# HSHV4-student_version.net
KiCad netlist of a schematic drawn in EAGLE
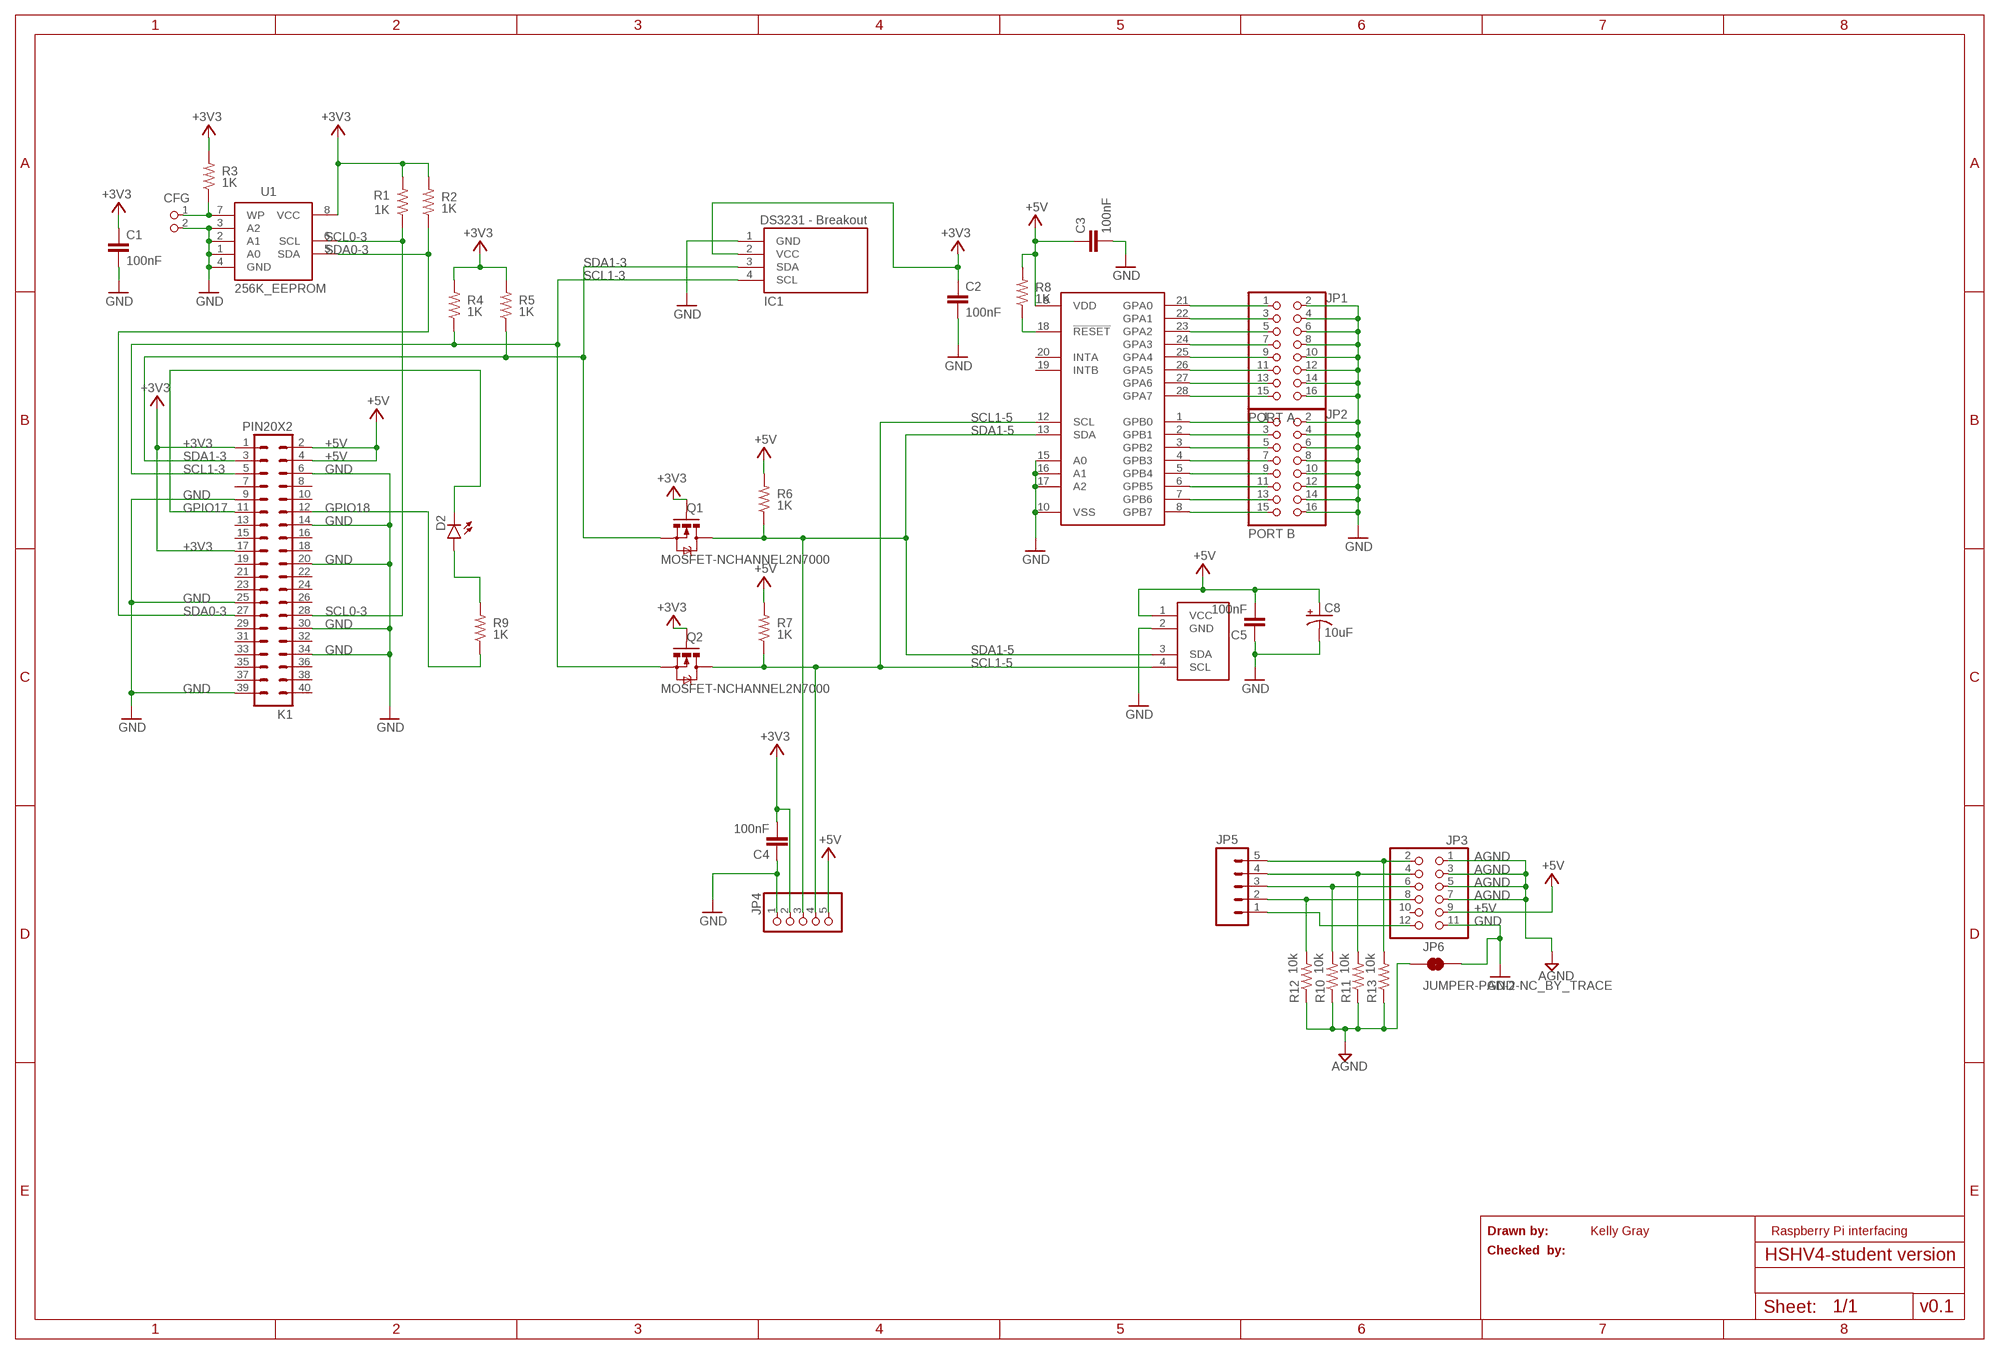
[diagram p0: schematic, sheet 1]

(export (version "E")
  (design (tool "Eeschema 10.0.6"))
  (components
    (comp (ref "C1")
      (value "100nF")
      (footprint "eagle-import:CAP-PTH-SMALL-KIT")
      (libsource (lib "eagle-import") (part "0.1UF-50V-20%(PTH)KIT-EZ"))
    )
    (comp (ref "C2")
      (value "100nF")
      (footprint "eagle-import:CAP-PTH-SMALL-KIT")
      (libsource (lib "eagle-import") (part "0.1UF-50V-20%(PTH)KIT-EZ"))
    )
    (comp (ref "C3")
      (value "100nF")
      (footprint "eagle-import:CAP-PTH-SMALL-KIT")
      (libsource (lib "eagle-import") (part "0.1UF-50V-20%(PTH)KIT-EZ"))
    )
    (comp (ref "C4")
      (value "100nF")
      (footprint "eagle-import:CAP-PTH-SMALL-KIT")
      (libsource (lib "eagle-import") (part "0.1UF-50V-20%(PTH)KIT-EZ"))
    )
    (comp (ref "C5")
      (value "100nF")
      (footprint "eagle-import:CAP-PTH-SMALL-KIT")
      (libsource (lib "eagle-import") (part "0.1UF-50V-20%(PTH)KIT-EZ"))
    )
    (comp (ref "C8")
      (value "10uF")
      (footprint "eagle-import:CPOL-RADIAL-10UF-25V")
      (libsource (lib "eagle-import") (part "10UF-25V-20%(PTH)"))
    )
    (comp (ref "CFG")
      (value "PIN2_100")
      (footprint "eagle-import:PIN_W_2")
      (libsource (lib "eagle-import") (part "PIN2_100"))
    )
    (comp (ref "D2")
      (value "LED-3MM-NO_SILK")
      (footprint "eagle-import:LED3MM-NS")
      (libsource (lib "eagle-import") (part "LED-3MM-NO_SILK"))
    )
    (comp (ref "IC1")
      (value "DS3231")
      (footprint "eagle-import:8PTH")
      (libsource (lib "eagle-import") (part "DS3231"))
    )
    (comp (ref "IC4")
      (value "IO_EXPANDER")
      (footprint "eagle-import:DIL28-3")
      (libsource (lib "eagle-import") (part "IO_EXPANDER"))
    )
    (comp (ref "JP1")
      (value "PORT A")
      (footprint "eagle-import:2X08")
      (libsource (lib "eagle-import") (part "PINHD-2X8"))
    )
    (comp (ref "JP2")
      (value "PORT B")
      (footprint "eagle-import:2X08")
      (libsource (lib "eagle-import") (part "PINHD-2X8"))
    )
    (comp (ref "JP3")
      (value "PINHD-2X6")
      (footprint "eagle-import:2X06")
      (libsource (lib "eagle-import") (part "PINHD-2X6"))
    )
    (comp (ref "JP4")
      (value "PINHD-1X5")
      (footprint "eagle-import:1X05")
      (libsource (lib "eagle-import") (part "PINHD-1X5"))
    )
    (comp (ref "JP5")
      (value "M05PTH")
      (footprint "eagle-import:1X05")
      (libsource (lib "eagle-import") (part "M05PTH"))
    )
    (comp (ref "JP6")
      (value "JUMPER-PAD-2-NC_BY_TRACE")
      (footprint "eagle-import:PAD-JUMPER-2-NC_BY_TRACE_YES_SILK")
      (libsource (lib "eagle-import") (part "JUMPER-PAD-2-NC_BY_TRACE"))
    )
    (comp (ref "K1")
      (value "PIN20X2")
      (footprint "eagle-import:PIN_20X2")
      (libsource (lib "eagle-import") (part "PIN20X2"))
    )
    (comp (ref "Q1")
      (value "MOSFET-NCHANNEL2N7000")
      (footprint "eagle-import:TO-92")
      (libsource (lib "eagle-import") (part "MOSFET-NCHANNEL2N7000"))
    )
    (comp (ref "Q2")
      (value "MOSFET-NCHANNEL2N7000")
      (footprint "eagle-import:TO-92")
      (libsource (lib "eagle-import") (part "MOSFET-NCHANNEL2N7000"))
    )
    (comp (ref "R1")
      (value "1K")
      (footprint "eagle-import:AXIAL-0.3")
      (fields (field (name "TOLERANCE") "5%"))
      (libsource (lib "eagle-import") (part "1KOHM-1/4W-1%(PTH)"))
    )
    (comp (ref "R2")
      (value "1K")
      (footprint "eagle-import:AXIAL-0.3")
      (fields (field (name "TOLERANCE") "5%"))
      (libsource (lib "eagle-import") (part "1KOHM-1/4W-1%(PTH)"))
    )
    (comp (ref "R3")
      (value "1K")
      (footprint "eagle-import:AXIAL-0.3")
      (fields (field (name "TOLERANCE") "5%"))
      (libsource (lib "eagle-import") (part "1KOHM-1/4W-1%(PTH)"))
    )
    (comp (ref "R4")
      (value "1K")
      (footprint "eagle-import:AXIAL-0.3")
      (fields (field (name "TOLERANCE") "5%"))
      (libsource (lib "eagle-import") (part "1KOHM-1/4W-1%(PTH)"))
    )
    (comp (ref "R5")
      (value "1K")
      (footprint "eagle-import:AXIAL-0.3")
      (fields (field (name "TOLERANCE") "5%"))
      (libsource (lib "eagle-import") (part "1KOHM-1/4W-1%(PTH)"))
    )
    (comp (ref "R6")
      (value "1K")
      (footprint "eagle-import:AXIAL-0.3")
      (fields (field (name "TOLERANCE") "5%"))
      (libsource (lib "eagle-import") (part "1KOHM-1/4W-1%(PTH)"))
    )
    (comp (ref "R7")
      (value "1K")
      (footprint "eagle-import:AXIAL-0.3")
      (fields (field (name "TOLERANCE") "5%"))
      (libsource (lib "eagle-import") (part "1KOHM-1/4W-1%(PTH)"))
    )
    (comp (ref "R8")
      (value "1K")
      (footprint "eagle-import:AXIAL-0.3")
      (fields (field (name "TOLERANCE") "5%"))
      (libsource (lib "eagle-import") (part "1KOHM-1/4W-1%(PTH)"))
    )
    (comp (ref "R9")
      (value "1K")
      (footprint "eagle-import:AXIAL-0.3")
      (fields (field (name "TOLERANCE") "5%"))
      (libsource (lib "eagle-import") (part "1KOHM-1/4W-1%(PTH)"))
    )
    (comp (ref "R10")
      (value "10k")
      (footprint "eagle-import:AXIAL-0.3")
      (fields (field (name "TOLERANCE") "5%"))
      (libsource (lib "eagle-import") (part "10KOHM-1/4W-1%(PTH)HORIZ"))
    )
    (comp (ref "R11")
      (value "10k")
      (footprint "eagle-import:AXIAL-0.3")
      (fields (field (name "TOLERANCE") "5%"))
      (libsource (lib "eagle-import") (part "10KOHM-1/4W-1%(PTH)HORIZ"))
    )
    (comp (ref "R12")
      (value "10k")
      (footprint "eagle-import:AXIAL-0.3")
      (fields (field (name "TOLERANCE") "5%"))
      (libsource (lib "eagle-import") (part "10KOHM-1/4W-1%(PTH)HORIZ"))
    )
    (comp (ref "R13")
      (value "10k")
      (footprint "eagle-import:AXIAL-0.3")
      (fields (field (name "TOLERANCE") "5%"))
      (libsource (lib "eagle-import") (part "10KOHM-1/4W-1%(PTH)HORIZ"))
    )
    (comp (ref "U$1")
      (value "PCF8591")
      (footprint "eagle-import:1X04")
      (libsource (lib "eagle-import") (part "PCF8591"))
    )
    (comp (ref "U1")
      (value "256K_EEPROM")
      (footprint "eagle-import:DIL08")
      (libsource (lib "eagle-import") (part "256K_EEPROM"))
    )
  )
  (nets
    (net (code "1") (name "+3V3") (class "Default")
      (node (ref "C1") (pin "1") (pinfunction "1_1") (pintype "passive"))
      (node (ref "C2") (pin "1") (pinfunction "1_1") (pintype "passive"))
      (node (ref "C4") (pin "2") (pinfunction "2_2") (pintype "passive"))
      (node (ref "IC1") (pin "2") (pinfunction "VCC_2") (pintype "power_in"))
      (node (ref "JP4") (pin "2") (pinfunction "2_2") (pintype "passive"))
      (node (ref "K1") (pin "1") (pinfunction "1_1") (pintype "passive"))
      (node (ref "K1") (pin "17") (pinfunction "17_17") (pintype "passive"))
      (node (ref "Q1") (pin "2") (pinfunction "G_2") (pintype "passive"))
      (node (ref "Q2") (pin "2") (pinfunction "G_2") (pintype "passive"))
      (node (ref "R1") (pin "P$2") (pinfunction "2_P$2") (pintype "passive"))
      (node (ref "R2") (pin "P$2") (pinfunction "2_P$2") (pintype "passive"))
      (node (ref "R3") (pin "P$2") (pinfunction "2_P$2") (pintype "passive"))
      (node (ref "R4") (pin "P$2") (pinfunction "2_P$2") (pintype "passive"))
      (node (ref "R5") (pin "P$2") (pinfunction "2_P$2") (pintype "passive"))
      (node (ref "U1") (pin "8") (pinfunction "VCC_8") (pintype "bidirectional"))
    )
    (net (code "2") (name "+5V") (class "Default")
      (node (ref "C3") (pin "1") (pinfunction "1_1") (pintype "passive"))
      (node (ref "C5") (pin "2") (pinfunction "2_2") (pintype "passive"))
      (node (ref "C8") (pin "1") (pinfunction "+_1") (pintype "passive"))
      (node (ref "IC4") (pin "9") (pinfunction "VDD_9") (pintype "bidirectional"))
      (node (ref "JP3") (pin "9") (pinfunction "9_9") (pintype "passive"))
      (node (ref "JP4") (pin "5") (pinfunction "5_5") (pintype "passive"))
      (node (ref "K1") (pin "2") (pinfunction "2_2") (pintype "passive"))
      (node (ref "K1") (pin "4") (pinfunction "4_4") (pintype "passive"))
      (node (ref "R6") (pin "P$2") (pinfunction "2_P$2") (pintype "passive"))
      (node (ref "R7") (pin "P$2") (pinfunction "2_P$2") (pintype "passive"))
      (node (ref "R8") (pin "P$2") (pinfunction "2_P$2") (pintype "passive"))
      (node (ref "U$1") (pin "1") (pinfunction "VCC_1") (pintype "bidirectional"))
    )
    (net (code "3") (name "/GPIO17") (class "Default")
      (node (ref "D2") (pin "K") (pinfunction "C_K") (pintype "passive"))
      (node (ref "K1") (pin "11") (pinfunction "11_11") (pintype "passive"))
    )
    (net (code "4") (name "/GPIO18") (class "Default")
      (node (ref "K1") (pin "12") (pinfunction "12_12") (pintype "passive"))
      (node (ref "R9") (pin "P$1") (pinfunction "1_P$1") (pintype "passive"))
    )
    (net (code "5") (name "/SCL0-3") (class "Default")
      (node (ref "K1") (pin "28") (pinfunction "28_28") (pintype "passive"))
      (node (ref "R1") (pin "P$1") (pinfunction "1_P$1") (pintype "passive"))
      (node (ref "U1") (pin "6") (pinfunction "SCL_6") (pintype "bidirectional"))
    )
    (net (code "6") (name "/SCL1-3") (class "Default")
      (node (ref "IC1") (pin "4") (pinfunction "SCL_4") (pintype "bidirectional"))
      (node (ref "K1") (pin "5") (pinfunction "5_5") (pintype "passive"))
      (node (ref "Q2") (pin "1") (pinfunction "S_1") (pintype "passive"))
      (node (ref "R4") (pin "P$1") (pinfunction "1_P$1") (pintype "passive"))
    )
    (net (code "7") (name "/SCL1-5") (class "Default")
      (node (ref "IC4") (pin "12") (pinfunction "SCL_12") (pintype "bidirectional"))
      (node (ref "JP4") (pin "4") (pinfunction "4_4") (pintype "passive"))
      (node (ref "Q2") (pin "3") (pinfunction "D_3") (pintype "passive"))
      (node (ref "R7") (pin "P$1") (pinfunction "1_P$1") (pintype "passive"))
      (node (ref "U$1") (pin "4") (pinfunction "SCL_4") (pintype "bidirectional"))
    )
    (net (code "8") (name "/SDA0-3") (class "Default")
      (node (ref "K1") (pin "27") (pinfunction "27_27") (pintype "passive"))
      (node (ref "R2") (pin "P$1") (pinfunction "1_P$1") (pintype "passive"))
      (node (ref "U1") (pin "5") (pinfunction "SDA_5") (pintype "bidirectional"))
    )
    (net (code "9") (name "/SDA1-3") (class "Default")
      (node (ref "IC1") (pin "3") (pinfunction "SDA_3") (pintype "bidirectional"))
      (node (ref "K1") (pin "3") (pinfunction "3_3") (pintype "passive"))
      (node (ref "Q1") (pin "1") (pinfunction "S_1") (pintype "passive"))
      (node (ref "R5") (pin "P$1") (pinfunction "1_P$1") (pintype "passive"))
    )
    (net (code "10") (name "/SDA1-5") (class "Default")
      (node (ref "IC4") (pin "13") (pinfunction "SDA_13") (pintype "bidirectional"))
      (node (ref "JP4") (pin "3") (pinfunction "3_3") (pintype "passive"))
      (node (ref "Q1") (pin "3") (pinfunction "D_3") (pintype "passive"))
      (node (ref "R6") (pin "P$1") (pinfunction "1_P$1") (pintype "passive"))
      (node (ref "U$1") (pin "3") (pinfunction "SDA_3") (pintype "bidirectional"))
    )
    (net (code "11") (name "AGND") (class "Default")
      (node (ref "JP3") (pin "1") (pinfunction "1_1") (pintype "passive"))
      (node (ref "JP3") (pin "3") (pinfunction "3_3") (pintype "passive"))
      (node (ref "JP3") (pin "5") (pinfunction "5_5") (pintype "passive"))
      (node (ref "JP3") (pin "7") (pinfunction "7_7") (pintype "passive"))
      (node (ref "JP6") (pin "1") (pinfunction "1_1") (pintype "passive"))
      (node (ref "R10") (pin "P$1") (pinfunction "1_P$1") (pintype "passive"))
      (node (ref "R11") (pin "P$1") (pinfunction "1_P$1") (pintype "passive"))
      (node (ref "R12") (pin "P$1") (pinfunction "1_P$1") (pintype "passive"))
      (node (ref "R13") (pin "P$1") (pinfunction "1_P$1") (pintype "passive"))
    )
    (net (code "12") (name "GND") (class "Default")
      (node (ref "C1") (pin "2") (pinfunction "2_2") (pintype "passive"))
      (node (ref "C2") (pin "2") (pinfunction "2_2") (pintype "passive"))
      (node (ref "C3") (pin "2") (pinfunction "2_2") (pintype "passive"))
      (node (ref "C4") (pin "1") (pinfunction "1_1") (pintype "passive"))
      (node (ref "C5") (pin "1") (pinfunction "1_1") (pintype "passive"))
      (node (ref "C8") (pin "2") (pinfunction "-_2") (pintype "passive"))
      (node (ref "CFG") (pin "2") (pinfunction "2_2") (pintype "passive"))
      (node (ref "IC1") (pin "1") (pinfunction "GND_1") (pintype "power_in"))
      (node (ref "IC4") (pin "10") (pinfunction "VSS_10") (pintype "bidirectional"))
      (node (ref "IC4") (pin "15") (pinfunction "A0_15") (pintype "bidirectional"))
      (node (ref "IC4") (pin "16") (pinfunction "A1_16") (pintype "bidirectional"))
      (node (ref "IC4") (pin "17") (pinfunction "A2_17") (pintype "bidirectional"))
      (node (ref "JP1") (pin "10") (pinfunction "10_10") (pintype "passive"))
      (node (ref "JP1") (pin "12") (pinfunction "12_12") (pintype "passive"))
      (node (ref "JP1") (pin "14") (pinfunction "14_14") (pintype "passive"))
      (node (ref "JP1") (pin "16") (pinfunction "16_16") (pintype "passive"))
      (node (ref "JP1") (pin "2") (pinfunction "2_2") (pintype "passive"))
      (node (ref "JP1") (pin "4") (pinfunction "4_4") (pintype "passive"))
      (node (ref "JP1") (pin "6") (pinfunction "6_6") (pintype "passive"))
      (node (ref "JP1") (pin "8") (pinfunction "8_8") (pintype "passive"))
      (node (ref "JP2") (pin "10") (pinfunction "10_10") (pintype "passive"))
      (node (ref "JP2") (pin "12") (pinfunction "12_12") (pintype "passive"))
      (node (ref "JP2") (pin "14") (pinfunction "14_14") (pintype "passive"))
      (node (ref "JP2") (pin "16") (pinfunction "16_16") (pintype "passive"))
      (node (ref "JP2") (pin "2") (pinfunction "2_2") (pintype "passive"))
      (node (ref "JP2") (pin "4") (pinfunction "4_4") (pintype "passive"))
      (node (ref "JP2") (pin "6") (pinfunction "6_6") (pintype "passive"))
      (node (ref "JP2") (pin "8") (pinfunction "8_8") (pintype "passive"))
      (node (ref "JP3") (pin "11") (pinfunction "11_11") (pintype "passive"))
      (node (ref "JP4") (pin "1") (pinfunction "1_1") (pintype "passive"))
      (node (ref "JP6") (pin "2") (pinfunction "2_2") (pintype "passive"))
      (node (ref "K1") (pin "14") (pinfunction "14_14") (pintype "passive"))
      (node (ref "K1") (pin "20") (pinfunction "20_20") (pintype "passive"))
      (node (ref "K1") (pin "25") (pinfunction "25_25") (pintype "passive"))
      (node (ref "K1") (pin "30") (pinfunction "30_30") (pintype "passive"))
      (node (ref "K1") (pin "34") (pinfunction "34_34") (pintype "passive"))
      (node (ref "K1") (pin "39") (pinfunction "39_39") (pintype "passive"))
      (node (ref "K1") (pin "6") (pinfunction "6_6") (pintype "passive"))
      (node (ref "K1") (pin "9") (pinfunction "9_9") (pintype "passive"))
      (node (ref "U$1") (pin "2") (pinfunction "GND_2") (pintype "bidirectional"))
      (node (ref "U1") (pin "1") (pinfunction "A0_1") (pintype "bidirectional"))
      (node (ref "U1") (pin "2") (pinfunction "A1_2") (pintype "bidirectional"))
      (node (ref "U1") (pin "3") (pinfunction "A2_3") (pintype "bidirectional"))
      (node (ref "U1") (pin "4") (pinfunction "GND_4") (pintype "bidirectional"))
    )
    (net (code "13") (name "Net-(IC4-GPA0)") (class "Default")
      (node (ref "IC4") (pin "21") (pinfunction "GPA0_21") (pintype "bidirectional"))
      (node (ref "JP1") (pin "1") (pinfunction "1_1") (pintype "passive"))
    )
    (net (code "14") (name "Net-(IC4-GPA1)") (class "Default")
      (node (ref "IC4") (pin "22") (pinfunction "GPA1_22") (pintype "bidirectional"))
      (node (ref "JP1") (pin "3") (pinfunction "3_3") (pintype "passive"))
    )
    (net (code "15") (name "Net-(IC4-GPA2)") (class "Default")
      (node (ref "IC4") (pin "23") (pinfunction "GPA2_23") (pintype "bidirectional"))
      (node (ref "JP1") (pin "5") (pinfunction "5_5") (pintype "passive"))
    )
    (net (code "16") (name "Net-(IC4-GPA3)") (class "Default")
      (node (ref "IC4") (pin "24") (pinfunction "GPA3_24") (pintype "bidirectional"))
      (node (ref "JP1") (pin "7") (pinfunction "7_7") (pintype "passive"))
    )
    (net (code "17") (name "Net-(IC4-GPA4)") (class "Default")
      (node (ref "IC4") (pin "25") (pinfunction "GPA4_25") (pintype "bidirectional"))
      (node (ref "JP1") (pin "9") (pinfunction "9_9") (pintype "passive"))
    )
    (net (code "18") (name "Net-(IC4-GPA5)") (class "Default")
      (node (ref "IC4") (pin "26") (pinfunction "GPA5_26") (pintype "bidirectional"))
      (node (ref "JP1") (pin "11") (pinfunction "11_11") (pintype "passive"))
    )
    (net (code "19") (name "Net-(IC4-GPA6)") (class "Default")
      (node (ref "IC4") (pin "27") (pinfunction "GPA6_27") (pintype "bidirectional"))
      (node (ref "JP1") (pin "13") (pinfunction "13_13") (pintype "passive"))
    )
    (net (code "20") (name "Net-(IC4-GPA7)") (class "Default")
      (node (ref "IC4") (pin "28") (pinfunction "GPA7_28") (pintype "bidirectional"))
      (node (ref "JP1") (pin "15") (pinfunction "15_15") (pintype "passive"))
    )
    (net (code "21") (name "Net-(IC4-GPB0)") (class "Default")
      (node (ref "IC4") (pin "1") (pinfunction "GPB0_1") (pintype "bidirectional"))
      (node (ref "JP2") (pin "1") (pinfunction "1_1") (pintype "passive"))
    )
    (net (code "22") (name "Net-(IC4-GPB1)") (class "Default")
      (node (ref "IC4") (pin "2") (pinfunction "GPB1_2") (pintype "bidirectional"))
      (node (ref "JP2") (pin "3") (pinfunction "3_3") (pintype "passive"))
    )
    (net (code "23") (name "Net-(IC4-GPB2)") (class "Default")
      (node (ref "IC4") (pin "3") (pinfunction "GPB2_3") (pintype "bidirectional"))
      (node (ref "JP2") (pin "5") (pinfunction "5_5") (pintype "passive"))
    )
    (net (code "24") (name "Net-(IC4-GPB3)") (class "Default")
      (node (ref "IC4") (pin "4") (pinfunction "GPB3_4") (pintype "bidirectional"))
      (node (ref "JP2") (pin "7") (pinfunction "7_7") (pintype "passive"))
    )
    (net (code "25") (name "Net-(IC4-GPB4)") (class "Default")
      (node (ref "IC4") (pin "5") (pinfunction "GPB4_5") (pintype "bidirectional"))
      (node (ref "JP2") (pin "9") (pinfunction "9_9") (pintype "passive"))
    )
    (net (code "26") (name "Net-(IC4-GPB5)") (class "Default")
      (node (ref "IC4") (pin "6") (pinfunction "GPB5_6") (pintype "bidirectional"))
      (node (ref "JP2") (pin "11") (pinfunction "11_11") (pintype "passive"))
    )
    (net (code "27") (name "Net-(IC4-GPB6)") (class "Default")
      (node (ref "IC4") (pin "7") (pinfunction "GPB6_7") (pintype "bidirectional"))
      (node (ref "JP2") (pin "13") (pinfunction "13_13") (pintype "passive"))
    )
    (net (code "28") (name "Net-(IC4-GPB7)") (class "Default")
      (node (ref "IC4") (pin "8") (pinfunction "GPB7_8") (pintype "bidirectional"))
      (node (ref "JP2") (pin "15") (pinfunction "15_15") (pintype "passive"))
    )
    (net (code "29") (name "Net-(IC4-~{RESET})") (class "Default")
      (node (ref "IC4") (pin "18") (pinfunction "~{RESET}_18") (pintype "bidirectional"))
      (node (ref "R8") (pin "P$1") (pinfunction "1_P$1") (pintype "passive"))
    )
    (net (code "30") (name "Net-(JP3-Pad12)") (class "Default")
      (node (ref "JP3") (pin "12") (pinfunction "12_12") (pintype "passive"))
      (node (ref "JP5") (pin "1") (pinfunction "1_1") (pintype "passive"))
    )
    (net (code "31") (name "Net-(R3-1)") (class "Default")
      (node (ref "CFG") (pin "1") (pinfunction "1_1") (pintype "passive"))
      (node (ref "R3") (pin "P$1") (pinfunction "1_P$1") (pintype "passive"))
      (node (ref "U1") (pin "7") (pinfunction "WP_7") (pintype "bidirectional"))
    )
    (net (code "32") (name "Net-(R9-2)") (class "Default")
      (node (ref "D2") (pin "A") (pinfunction "A_A") (pintype "passive"))
      (node (ref "R9") (pin "P$2") (pinfunction "2_P$2") (pintype "passive"))
    )
    (net (code "33") (name "Net-(R10-2)") (class "Default")
      (node (ref "JP3") (pin "6") (pinfunction "6_6") (pintype "passive"))
      (node (ref "JP5") (pin "3") (pinfunction "3_3") (pintype "passive"))
      (node (ref "R10") (pin "P$2") (pinfunction "2_P$2") (pintype "passive"))
    )
    (net (code "34") (name "Net-(R11-2)") (class "Default")
      (node (ref "JP3") (pin "4") (pinfunction "4_4") (pintype "passive"))
      (node (ref "JP5") (pin "4") (pinfunction "4_4") (pintype "passive"))
      (node (ref "R11") (pin "P$2") (pinfunction "2_P$2") (pintype "passive"))
    )
    (net (code "35") (name "Net-(R12-2)") (class "Default")
      (node (ref "JP3") (pin "8") (pinfunction "8_8") (pintype "passive"))
      (node (ref "JP5") (pin "2") (pinfunction "2_2") (pintype "passive"))
      (node (ref "R12") (pin "P$2") (pinfunction "2_P$2") (pintype "passive"))
    )
    (net (code "36") (name "Net-(R13-2)") (class "Default")
      (node (ref "JP3") (pin "2") (pinfunction "2_2") (pintype "passive"))
      (node (ref "JP5") (pin "5") (pinfunction "5_5") (pintype "passive"))
      (node (ref "R13") (pin "P$2") (pinfunction "2_P$2") (pintype "passive"))
    )
    (net (code "37") (name "unconnected-(IC4-INTA-Pad20)") (class "Default")
      (node (ref "IC4") (pin "20") (pinfunction "INTA_20") (pintype "bidirectional"))
    )
    (net (code "38") (name "unconnected-(IC4-INTB-Pad19)") (class "Default")
      (node (ref "IC4") (pin "19") (pinfunction "INTB_19") (pintype "bidirectional"))
    )
    (net (code "39") (name "unconnected-(JP3-Pad10)") (class "Default")
      (node (ref "JP3") (pin "10") (pinfunction "10_10") (pintype "passive"))
    )
    (net (code "40") (name "unconnected-(K1-Pad7)") (class "Default")
      (node (ref "K1") (pin "7") (pinfunction "7_7") (pintype "passive"))
    )
    (net (code "41") (name "unconnected-(K1-Pad8)") (class "Default")
      (node (ref "K1") (pin "8") (pinfunction "8_8") (pintype "passive"))
    )
    (net (code "42") (name "unconnected-(K1-Pad10)") (class "Default")
      (node (ref "K1") (pin "10") (pinfunction "10_10") (pintype "passive"))
    )
    (net (code "43") (name "unconnected-(K1-Pad13)") (class "Default")
      (node (ref "K1") (pin "13") (pinfunction "13_13") (pintype "passive"))
    )
    (net (code "44") (name "unconnected-(K1-Pad15)") (class "Default")
      (node (ref "K1") (pin "15") (pinfunction "15_15") (pintype "passive"))
    )
    (net (code "45") (name "unconnected-(K1-Pad16)") (class "Default")
      (node (ref "K1") (pin "16") (pinfunction "16_16") (pintype "passive"))
    )
    (net (code "46") (name "unconnected-(K1-Pad18)") (class "Default")
      (node (ref "K1") (pin "18") (pinfunction "18_18") (pintype "passive"))
    )
    (net (code "47") (name "unconnected-(K1-Pad19)") (class "Default")
      (node (ref "K1") (pin "19") (pinfunction "19_19") (pintype "passive"))
    )
    (net (code "48") (name "unconnected-(K1-Pad21)") (class "Default")
      (node (ref "K1") (pin "21") (pinfunction "21_21") (pintype "passive"))
    )
    (net (code "49") (name "unconnected-(K1-Pad22)") (class "Default")
      (node (ref "K1") (pin "22") (pinfunction "22_22") (pintype "passive"))
    )
    (net (code "50") (name "unconnected-(K1-Pad23)") (class "Default")
      (node (ref "K1") (pin "23") (pinfunction "23_23") (pintype "passive"))
    )
    (net (code "51") (name "unconnected-(K1-Pad24)") (class "Default")
      (node (ref "K1") (pin "24") (pinfunction "24_24") (pintype "passive"))
    )
    (net (code "52") (name "unconnected-(K1-Pad26)") (class "Default")
      (node (ref "K1") (pin "26") (pinfunction "26_26") (pintype "passive"))
    )
    (net (code "53") (name "unconnected-(K1-Pad29)") (class "Default")
      (node (ref "K1") (pin "29") (pinfunction "29_29") (pintype "passive"))
    )
    (net (code "54") (name "unconnected-(K1-Pad31)") (class "Default")
      (node (ref "K1") (pin "31") (pinfunction "31_31") (pintype "passive"))
    )
    (net (code "55") (name "unconnected-(K1-Pad32)") (class "Default")
      (node (ref "K1") (pin "32") (pinfunction "32_32") (pintype "passive"))
    )
    (net (code "56") (name "unconnected-(K1-Pad33)") (class "Default")
      (node (ref "K1") (pin "33") (pinfunction "33_33") (pintype "passive"))
    )
    (net (code "57") (name "unconnected-(K1-Pad35)") (class "Default")
      (node (ref "K1") (pin "35") (pinfunction "35_35") (pintype "passive"))
    )
    (net (code "58") (name "unconnected-(K1-Pad36)") (class "Default")
      (node (ref "K1") (pin "36") (pinfunction "36_36") (pintype "passive"))
    )
    (net (code "59") (name "unconnected-(K1-Pad37)") (class "Default")
      (node (ref "K1") (pin "37") (pinfunction "37_37") (pintype "passive"))
    )
    (net (code "60") (name "unconnected-(K1-Pad38)") (class "Default")
      (node (ref "K1") (pin "38") (pinfunction "38_38") (pintype "passive"))
    )
    (net (code "61") (name "unconnected-(K1-Pad40)") (class "Default")
      (node (ref "K1") (pin "40") (pinfunction "40_40") (pintype "passive"))
    )
  )
)
